# PELT_DRIVE.net
KiCad netlist of a schematic drawn in Altium Designer
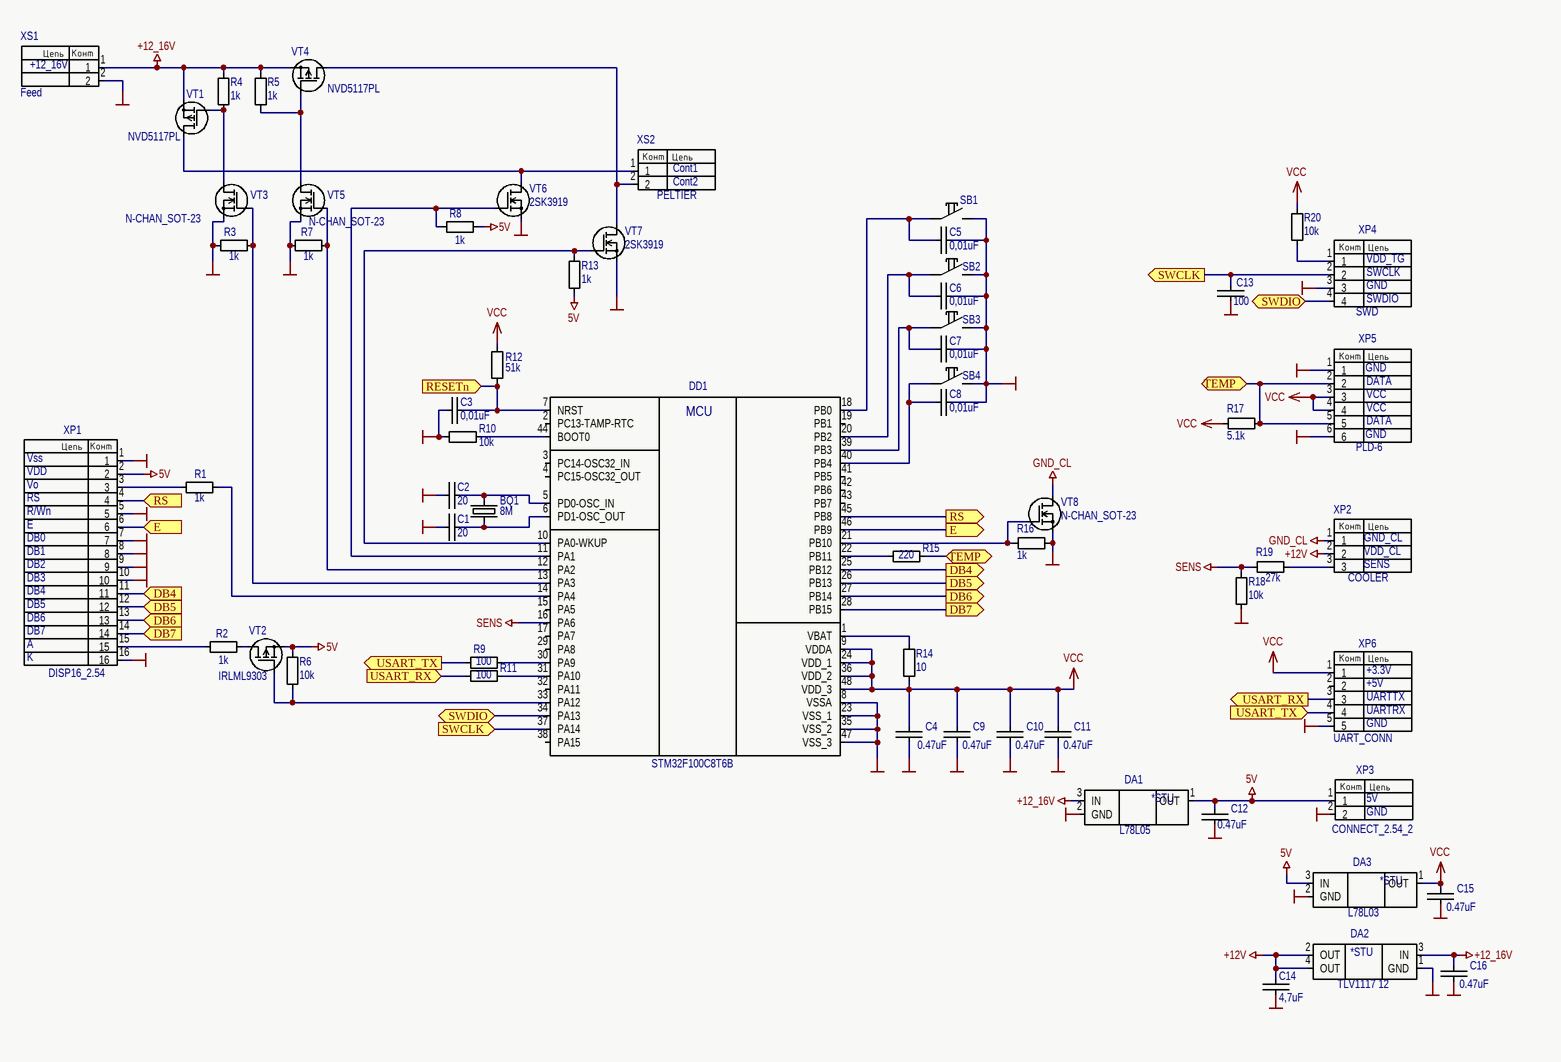
[diagram p0: PELT_DRIVE.SchDoc]

(export (version "E")
  (design (tool "Eeschema 10.0.6"))
  (components
    (comp (ref "BQ1") (value "8M") (footprint "HC 49S") (libsource (lib "PANEL") (part "BQ_HC 49S")))
    (comp (ref "C1")
      (value "20")
      (footprint "Cap_0805")
      (fields (field (name "MANUFACTURER") "AVX") (field (name "PART NUMBER") "08051A200JAT2A"))
      (libsource (lib "PANEL") (part "Cap_0805"))
    )
    (comp (ref "C2")
      (value "20")
      (footprint "Cap_0805")
      (fields (field (name "MANUFACTURER") "AVX") (field (name "PART NUMBER") "08051A200JAT2A"))
      (libsource (lib "PANEL") (part "Cap_0805"))
    )
    (comp (ref "C3")
      (value "0,01uF")
      (footprint "Cap_0805")
      (fields (field (name "MANUFACTURER") "AVX") (field (name "PART NUMBER") "08055C103JAT2A"))
      (libsource (lib "PANEL") (part "Cap_0805"))
    )
    (comp (ref "C4")
      (value "0.47uF")
      (footprint "Cap_0805")
      (fields (field (name "MANUFACTURER") "AVX") (field (name "PART NUMBER") "0805YC475KAT2A"))
      (libsource (lib "PANEL") (part "Cap_0805"))
    )
    (comp (ref "C5")
      (value "0,01uF")
      (footprint "Cap_0805")
      (fields (field (name "MANUFACTURER") "AVX") (field (name "PART NUMBER") "08055C103JAT2A"))
      (libsource (lib "PANEL") (part "Cap_0805"))
    )
    (comp (ref "C6")
      (value "0,01uF")
      (footprint "Cap_0805")
      (fields (field (name "MANUFACTURER") "AVX") (field (name "PART NUMBER") "08055C103JAT2A"))
      (libsource (lib "PANEL") (part "Cap_0805"))
    )
    (comp (ref "C7")
      (value "0,01uF")
      (footprint "Cap_0805")
      (fields (field (name "MANUFACTURER") "AVX") (field (name "PART NUMBER") "08055C103JAT2A"))
      (libsource (lib "PANEL") (part "Cap_0805"))
    )
    (comp (ref "C8")
      (value "0,01uF")
      (footprint "Cap_0805")
      (fields (field (name "MANUFACTURER") "AVX") (field (name "PART NUMBER") "08055C103JAT2A"))
      (libsource (lib "PANEL") (part "Cap_0805"))
    )
    (comp (ref "C9")
      (value "0.47uF")
      (footprint "Cap_0805")
      (fields (field (name "MANUFACTURER") "AVX") (field (name "PART NUMBER") "0805YC475KAT2A"))
      (libsource (lib "PANEL") (part "Cap_0805"))
    )
    (comp (ref "C10")
      (value "0.47uF")
      (footprint "Cap_0805")
      (fields (field (name "MANUFACTURER") "AVX") (field (name "PART NUMBER") "0805YC475KAT2A"))
      (libsource (lib "PANEL") (part "Cap_0805"))
    )
    (comp (ref "C11")
      (value "0.47uF")
      (footprint "Cap_0805")
      (fields (field (name "MANUFACTURER") "AVX") (field (name "PART NUMBER") "0805YC475KAT2A"))
      (libsource (lib "PANEL") (part "Cap_0805"))
    )
    (comp (ref "C12")
      (value "0.47uF")
      (footprint "Cap_0805")
      (fields (field (name "MANUFACTURER") "AVX") (field (name "PART NUMBER") "0805YC475KAT2A"))
      (libsource (lib "PANEL") (part "Cap_0805"))
    )
    (comp (ref "C13")
      (value "100")
      (footprint "Cap_0805")
      (fields (field (name "MANUFACTURER") "AVX") (field (name "PART NUMBER") "08055C101KAT2A"))
      (libsource (lib "PANEL") (part "Cap_0805"))
    )
    (comp (ref "C14")
      (value "4,7uF")
      (footprint "Cap_0805")
      (description "4.7uF 25V X7R 10%")
      (fields (field (name "MANUFACTURER") "AVX") (field (name "PART NUMBER") "0805YC475KAT2A"))
      (libsource (lib "PANEL") (part "Cap_0805"))
    )
    (comp (ref "C15")
      (value "0.47uF")
      (footprint "Cap_0805")
      (fields (field (name "MANUFACTURER") "AVX") (field (name "PART NUMBER") "0805YC475KAT2A"))
      (libsource (lib "PANEL") (part "Cap_0805"))
    )
    (comp (ref "C16")
      (value "0.47uF")
      (footprint "Cap_0805")
      (fields (field (name "MANUFACTURER") "AVX") (field (name "PART NUMBER") "0805YC475KAT2A"))
      (libsource (lib "PANEL") (part "Cap_0805"))
    )
    (comp (ref "DA1") (value "L78L05") (footprint "kren") (libsource (lib "PANEL") (part "kren")))
    (comp (ref "DA2")
      (value "TLV1117 12")
      (footprint "SOT223")
      (description "TLV1117-sot223")
      (fields (field (name "MANUFACTURER") "Microchip") (field (name "PART NUMBER") "TLV1117"))
      (libsource (lib "EIGHT_29") (part "TLV1117"))
    )
    (comp (ref "DA3")
      (value "L78L03")
      (footprint "kren")
      (fields (field (name "PART NUMBER") "L78L05"))
      (libsource (lib "PANEL") (part "kren"))
    )
    (comp (ref "DD1")
      (value "STM32F100C8T6B")
      (footprint "LQFP48")
      (fields (field (name "MANUFACTURER") "Manufacturer") (field (name "PART NUMBER") "Part Number"))
      (libsource (lib "PANEL") (part "STM32F100C8T6B"))
    )
    (comp (ref "R1") (value "1k") (footprint "Res_0805") (libsource (lib "PANEL") (part "Res_0805")))
    (comp (ref "R2") (value "1k") (footprint "Res_0805") (libsource (lib "PANEL") (part "Res_0805")))
    (comp (ref "R3") (value "1k") (footprint "Res_0805") (libsource (lib "PANEL") (part "Res_0805")))
    (comp (ref "R4")
      (value "1k")
      (footprint "Res_0805")
      (fields (field (name "MANUFACTURER") "Vishay") (field (name "PART NUMBER") "SMD 0805"))
      (libsource (lib "") (part "Res_0805_1"))
    )
    (comp (ref "R5") (value "1k") (footprint "Res_0805") (libsource (lib "") (part "Res_0805_1")))
    (comp (ref "R6")
      (value "10k")
      (footprint "Res_0805")
      (fields (field (name "MANUFACTURER") "Vishay") (field (name "PART NUMBER") "CRCW080510K0JNTA"))
      (libsource (lib "PANEL") (part "Res_0805"))
    )
    (comp (ref "R7") (value "1k") (footprint "Res_0805") (libsource (lib "PANEL") (part "Res_0805")))
    (comp (ref "R8")
      (value "1k")
      (footprint "Res_0805")
      (fields (field (name "PART NUMBER") "0805 1k"))
      (libsource (lib "PANEL") (part "Res_0805"))
    )
    (comp (ref "R9") (value "100") (footprint "Res_0805") (libsource (lib "PANEL") (part "Res_0805")))
    (comp (ref "R10")
      (value "10k")
      (footprint "Res_0805")
      (fields (field (name "MANUFACTURER") "Vishay") (field (name "PART NUMBER") "CRCW080510K0JNTA"))
      (libsource (lib "PANEL") (part "Res_0805"))
    )
    (comp (ref "R11") (value "100") (footprint "Res_0805") (libsource (lib "PANEL") (part "Res_0805")))
    (comp (ref "R12")
      (value "51k")
      (footprint "Res_0805")
      (fields (field (name "MANUFACTURER") "Vishay") (field (name "PART NUMBER") "CRCW08055K00JNTA"))
      (libsource (lib "PANEL") (part "Res_0805"))
    )
    (comp (ref "R13")
      (value "1k")
      (footprint "Res_0805")
      (fields (field (name "PART NUMBER") "0805 1k"))
      (libsource (lib "PANEL") (part "Res_0805"))
    )
    (comp (ref "R14")
      (value "10")
      (footprint "Res_0805")
      (fields (field (name "MANUFACTURER") "Vishay") (field (name "PART NUMBER") "CRCW080510R0FKEA"))
      (libsource (lib "PANEL") (part "Res_0805"))
    )
    (comp (ref "R15") (value "220") (footprint "Res_0805") (libsource (lib "PANEL") (part "Res_0805")))
    (comp (ref "R16") (value "1k") (footprint "Res_0805") (libsource (lib "PANEL") (part "Res_0805")))
    (comp (ref "R17")
      (value "5.1k")
      (footprint "Res_0805")
      (fields (field (name "MANUFACTURER") "Vishay") (field (name "PART NUMBER") "CRCW08055K10JNTA"))
      (libsource (lib "PANEL") (part "Res_0805"))
    )
    (comp (ref "R18")
      (value "10k")
      (footprint "Res_0805")
      (fields (field (name "MANUFACTURER") "Vishay") (field (name "PART NUMBER") "CRCW080510K0JNTA"))
      (libsource (lib "PANEL") (part "Res_0805"))
    )
    (comp (ref "R19")
      (value "27k")
      (footprint "Res_0805")
      (fields (field (name "MANUFACTURER") "Vishay") (field (name "PART NUMBER") "CRCW080527K0JNTA"))
      (libsource (lib "PANEL") (part "Res_0805"))
    )
    (comp (ref "R20")
      (value "10k")
      (footprint "Res_0805")
      (fields (field (name "MANUFACTURER") "Vishay") (field (name "PART NUMBER") "CRCW080510K0JNTA"))
      (libsource (lib "PANEL") (part "Res_0805"))
    )
    (comp (ref "SB1")
      (value "BUTTON 4.5x6")
      (footprint "BUTTON 6x4.5")
      (description "Button")
      (libsource (lib "PELT_DRIVE") (part "BUTTON 4.5x6"))
    )
    (comp (ref "SB2")
      (value "BUTTON 4.5x6")
      (footprint "BUTTON 6x4.5")
      (description "Button")
      (libsource (lib "") (part "BUTTON 4.5x6_1"))
    )
    (comp (ref "SB3")
      (value "BUTTON 4.5x6")
      (footprint "BUTTON 6x4.5")
      (description "Button")
      (libsource (lib "") (part "BUTTON 4.5x6_1"))
    )
    (comp (ref "SB4")
      (value "BUTTON 4.5x6")
      (footprint "BUTTON 6x4.5")
      (description "Button")
      (libsource (lib "") (part "BUTTON 4.5x6_1"))
    )
    (comp (ref "VT1")
      (value "NVD5117PL")
      (footprint "TO-252")
      (libsource (lib "PANEL") (part "P-CHAN_TO-252"))
    )
    (comp (ref "VT2")
      (value "IRLML9303")
      (footprint "SOT-23")
      (fields (field (name "PART NUMBER") "IRLML9303TRPBF"))
      (libsource (lib "PSU") (part "P-CHAN_SOT-23"))
    )
    (comp (ref "VT3")
      (value "N-CHAN_SOT-23")
      (footprint "SOT-23")
      (libsource (lib "PANEL") (part "N-CHAN_SOT-23"))
    )
    (comp (ref "VT4") (value "NVD5117PL") (footprint "TO-252") (libsource (lib "") (part "P-CHAN_TO-252_1")))
    (comp (ref "VT5")
      (value "N-CHAN_SOT-23")
      (footprint "SOT-23")
      (libsource (lib "PANEL") (part "N-CHAN_SOT-23"))
    )
    (comp (ref "VT6") (value "2SK3919") (footprint "TO-252") (libsource (lib "PANEL") (part "N-CHAN_TO-252")))
    (comp (ref "VT7") (value "2SK3919") (footprint "TO-252") (libsource (lib "PANEL") (part "N-CHAN_TO-252")))
    (comp (ref "VT8")
      (value "N-CHAN_SOT-23")
      (footprint "SOT-23")
      (libsource (lib "PANEL") (part "N-CHAN_SOT-23"))
    )
    (comp (ref "XP1")
      (value "DISP16_2.54")
      (footprint "DISP16_2.54")
      (libsource (lib "PANEL") (part "DISP16_2.54"))
    )
    (comp (ref "XP2")
      (value "COOLER")
      (footprint "CONN_2.54_3")
      (libsource (lib "PELT_DRIVE") (part "CONNECT_2.54_3"))
    )
    (comp (ref "XP3")
      (value "CONNECT_2.54_2")
      (footprint "CONN_2.54_2")
      (libsource (lib "PANEL") (part "CONNECT_2.54_2"))
    )
    (comp (ref "XP4")
      (value "SWD")
      (footprint "CONN_2.54_4")
      (fields (field (name "MANUFACTURER") "Manufacturer") (field (name "PART NUMBER") "Part Number"))
      (libsource (lib "PANEL") (part "CONNECT_SWD"))
    )
    (comp (ref "XP5")
      (value "PLD-6")
      (footprint "CONN_2.54_6_2")
      (libsource (lib "PANEL") (part "CONNECT_2.54_6_2"))
    )
    (comp (ref "XP6")
      (value "UART_CONN")
      (footprint "CONN_2.54_5")
      (libsource (lib "PANEL") (part "CONNECT_2.54_5"))
    )
    (comp (ref "XS1") (value "Feed") (footprint "PELTIER") (libsource (lib "PANEL") (part "PELTIER")))
    (comp (ref "XS2") (value "PELTIER") (footprint "PELTIER") (libsource (lib "") (part "PELTIER_1")))
  )
  (nets
    (net (code "1") (name "+12V") (class "Default")
      (node (ref "C14") (pin "2") (pinfunction "2_2") (pintype "passive"))
      (node (ref "DA2") (pin "2") (pinfunction "OUT_2") (pintype "passive"))
      (node (ref "DA2") (pin "4") (pinfunction "OUT_4") (pintype "passive"))
      (node (ref "XP2") (pin "2") (pinfunction "2_2") (pintype "passive"))
    )
    (net (code "2") (name "+12_16V") (class "Default")
      (node (ref "C16") (pin "2") (pinfunction "2_2") (pintype "passive"))
      (node (ref "DA1") (pin "3") (pinfunction "IN_3") (pintype "passive"))
      (node (ref "DA2") (pin "3") (pinfunction "IN_3") (pintype "passive"))
      (node (ref "R4") (pin "1") (pinfunction "1_1") (pintype "passive"))
      (node (ref "R5") (pin "2") (pinfunction "2_2") (pintype "passive"))
      (node (ref "VT1") (pin "3") (pinfunction "3_3") (pintype "passive"))
      (node (ref "VT4") (pin "3") (pinfunction "3_3") (pintype "passive"))
      (node (ref "XS1") (pin "1") (pinfunction "1_1") (pintype "passive"))
    )
    (net (code "3") (name "/DB4") (class "Default")
      (node (ref "DD1") (pin "25") (pinfunction "PB12_25") (pintype "passive"))
      (node (ref "XP1") (pin "11") (pinfunction "11_11") (pintype "passive"))
    )
    (net (code "4") (name "/DB5") (class "Default")
      (node (ref "DD1") (pin "26") (pinfunction "PB13_26") (pintype "passive"))
      (node (ref "XP1") (pin "12") (pinfunction "12_12") (pintype "passive"))
    )
    (net (code "5") (name "/DB6") (class "Default")
      (node (ref "DD1") (pin "27") (pinfunction "PB14_27") (pintype "passive"))
      (node (ref "XP1") (pin "13") (pinfunction "13_13") (pintype "passive"))
    )
    (net (code "6") (name "/DB7") (class "Default")
      (node (ref "DD1") (pin "28") (pinfunction "PB15_28") (pintype "passive"))
      (node (ref "XP1") (pin "14") (pinfunction "14_14") (pintype "passive"))
    )
    (net (code "7") (name "/E") (class "Default")
      (node (ref "DD1") (pin "46") (pinfunction "PB9_46") (pintype "passive"))
      (node (ref "XP1") (pin "6") (pinfunction "6_6") (pintype "passive"))
    )
    (net (code "8") (name "/RESETn") (class "Default")
      (node (ref "C3") (pin "2") (pinfunction "2_2") (pintype "passive"))
      (node (ref "DD1") (pin "7") (pinfunction "NRST_7") (pintype "passive"))
      (node (ref "R12") (pin "1") (pinfunction "1_1") (pintype "passive"))
    )
    (net (code "9") (name "/RS") (class "Default")
      (node (ref "DD1") (pin "45") (pinfunction "PB8_45") (pintype "passive"))
      (node (ref "XP1") (pin "4") (pinfunction "4_4") (pintype "passive"))
    )
    (net (code "10") (name "/SWCLK") (class "Default")
      (node (ref "C13") (pin "2") (pinfunction "2_2") (pintype "passive"))
      (node (ref "DD1") (pin "37") (pinfunction "PA14_37") (pintype "passive"))
      (node (ref "XP4") (pin "2") (pinfunction "2_2") (pintype "passive"))
    )
    (net (code "11") (name "/SWDIO") (class "Default")
      (node (ref "DD1") (pin "34") (pinfunction "PA13_34") (pintype "passive"))
      (node (ref "XP4") (pin "4") (pinfunction "4_4") (pintype "passive"))
    )
    (net (code "12") (name "/TEMP") (class "Default")
      (node (ref "R15") (pin "1") (pinfunction "1_1") (pintype "passive"))
      (node (ref "R17") (pin "1") (pinfunction "1_1") (pintype "passive"))
      (node (ref "XP5") (pin "2") (pinfunction "2_2") (pintype "passive"))
      (node (ref "XP5") (pin "5") (pinfunction "5_5") (pintype "passive"))
    )
    (net (code "13") (name "/USART_RX") (class "Default")
      (node (ref "R11") (pin "1") (pinfunction "1_1") (pintype "passive"))
      (node (ref "XP6") (pin "3") (pinfunction "3_3") (pintype "passive"))
    )
    (net (code "14") (name "/USART_TX") (class "Default")
      (node (ref "R9") (pin "1") (pinfunction "1_1") (pintype "passive"))
      (node (ref "XP6") (pin "4") (pinfunction "4_4") (pintype "passive"))
    )
    (net (code "15") (name "5V") (class "Default")
      (node (ref "C12") (pin "2") (pinfunction "2_2") (pintype "passive"))
      (node (ref "DA1") (pin "1") (pinfunction "OUT_1") (pintype "passive"))
      (node (ref "DA3") (pin "3") (pinfunction "IN_3") (pintype "passive"))
      (node (ref "R13") (pin "1") (pinfunction "1_1") (pintype "passive"))
      (node (ref "R6") (pin "1") (pinfunction "1_1") (pintype "passive"))
      (node (ref "R8") (pin "2") (pinfunction "2_2") (pintype "passive"))
      (node (ref "VT2") (pin "2") (pinfunction "2_2") (pintype "passive"))
      (node (ref "XP1") (pin "2") (pinfunction "2_2") (pintype "passive"))
      (node (ref "XP3") (pin "1") (pinfunction "1_1") (pintype "passive"))
    )
    (net (code "16") (name "GND") (class "Default")
      (node (ref "C1") (pin "1") (pinfunction "1_1") (pintype "passive"))
      (node (ref "C10") (pin "1") (pinfunction "1_1") (pintype "passive"))
      (node (ref "C11") (pin "1") (pinfunction "1_1") (pintype "passive"))
      (node (ref "C12") (pin "1") (pinfunction "1_1") (pintype "passive"))
      (node (ref "C13") (pin "1") (pinfunction "1_1") (pintype "passive"))
      (node (ref "C14") (pin "1") (pinfunction "1_1") (pintype "passive"))
      (node (ref "C15") (pin "1") (pinfunction "1_1") (pintype "passive"))
      (node (ref "C16") (pin "1") (pinfunction "1_1") (pintype "passive"))
      (node (ref "C2") (pin "1") (pinfunction "1_1") (pintype "passive"))
      (node (ref "C3") (pin "1") (pinfunction "1_1") (pintype "passive"))
      (node (ref "C4") (pin "1") (pinfunction "1_1") (pintype "passive"))
      (node (ref "C5") (pin "2") (pinfunction "2_2") (pintype "passive"))
      (node (ref "C6") (pin "2") (pinfunction "2_2") (pintype "passive"))
      (node (ref "C7") (pin "2") (pinfunction "2_2") (pintype "passive"))
      (node (ref "C8") (pin "2") (pinfunction "2_2") (pintype "passive"))
      (node (ref "C9") (pin "1") (pinfunction "1_1") (pintype "passive"))
      (node (ref "DA1") (pin "2") (pinfunction "GND_2") (pintype "passive"))
      (node (ref "DA2") (pin "1") (pinfunction "GND_1") (pintype "passive"))
      (node (ref "DA3") (pin "2") (pinfunction "GND_2") (pintype "passive"))
      (node (ref "DD1") (pin "23") (pinfunction "VSS_1_23") (pintype "passive"))
      (node (ref "DD1") (pin "35") (pinfunction "VSS_2_35") (pintype "passive"))
      (node (ref "DD1") (pin "47") (pinfunction "VSS_3_47") (pintype "passive"))
      (node (ref "DD1") (pin "8") (pinfunction "VSSA_8") (pintype "passive"))
      (node (ref "R10") (pin "2") (pinfunction "2_2") (pintype "passive"))
      (node (ref "R16") (pin "2") (pinfunction "2_2") (pintype "passive"))
      (node (ref "R18") (pin "1") (pinfunction "1_1") (pintype "passive"))
      (node (ref "R3") (pin "2") (pinfunction "2_2") (pintype "passive"))
      (node (ref "R7") (pin "1") (pinfunction "1_1") (pintype "passive"))
      (node (ref "SB1") (pin "2") (pinfunction "IN_2") (pintype "passive"))
      (node (ref "SB2") (pin "2") (pinfunction "IN_2") (pintype "passive"))
      (node (ref "SB3") (pin "2") (pinfunction "IN_2") (pintype "passive"))
      (node (ref "SB4") (pin "2") (pinfunction "IN_2") (pintype "passive"))
      (node (ref "VT3") (pin "2") (pinfunction "2_2") (pintype "passive"))
      (node (ref "VT5") (pin "2") (pinfunction "2_2") (pintype "passive"))
      (node (ref "VT6") (pin "3") (pinfunction "3_3") (pintype "passive"))
      (node (ref "VT7") (pin "3") (pinfunction "3_3") (pintype "passive"))
      (node (ref "VT8") (pin "2") (pinfunction "2_2") (pintype "passive"))
      (node (ref "XP1") (pin "1") (pinfunction "1_1") (pintype "passive"))
      (node (ref "XP1") (pin "10") (pinfunction "10_10") (pintype "passive"))
      (node (ref "XP1") (pin "16") (pinfunction "16_16") (pintype "passive"))
      (node (ref "XP1") (pin "5") (pinfunction "5_5") (pintype "passive"))
      (node (ref "XP1") (pin "7") (pinfunction "7_7") (pintype "passive"))
      (node (ref "XP1") (pin "8") (pinfunction "8_8") (pintype "passive"))
      (node (ref "XP1") (pin "9") (pinfunction "9_9") (pintype "passive"))
      (node (ref "XP3") (pin "2") (pinfunction "2_2") (pintype "passive"))
      (node (ref "XP4") (pin "3") (pinfunction "3_3") (pintype "passive"))
      (node (ref "XP5") (pin "1") (pinfunction "1_1") (pintype "passive"))
      (node (ref "XP5") (pin "6") (pinfunction "6_6") (pintype "passive"))
      (node (ref "XP6") (pin "5") (pinfunction "5_5") (pintype "passive"))
      (node (ref "XS1") (pin "2") (pinfunction "2_2") (pintype "passive"))
    )
    (net (code "17") (name "GND_CL") (class "Default")
      (node (ref "VT8") (pin "3") (pinfunction "3_3") (pintype "passive"))
      (node (ref "XP2") (pin "1") (pinfunction "1_1") (pintype "passive"))
    )
    (net (code "18") (name "Net-(DD1-BOOT0)") (class "Default")
      (node (ref "DD1") (pin "44") (pinfunction "BOOT0_44") (pintype "passive"))
      (node (ref "R10") (pin "1") (pinfunction "1_1") (pintype "passive"))
    )
    (net (code "19") (name "Net-(DD1-PA0-WKUP)") (class "Default")
      (node (ref "DD1") (pin "10") (pinfunction "PA0-WKUP_10") (pintype "passive"))
      (node (ref "R13") (pin "2") (pinfunction "2_2") (pintype "passive"))
      (node (ref "VT7") (pin "1") (pinfunction "1_1") (pintype "passive"))
    )
    (net (code "20") (name "Net-(DD1-PA1)") (class "Default")
      (node (ref "DD1") (pin "11") (pinfunction "PA1_11") (pintype "passive"))
      (node (ref "R8") (pin "1") (pinfunction "1_1") (pintype "passive"))
      (node (ref "VT6") (pin "1") (pinfunction "1_1") (pintype "passive"))
    )
    (net (code "21") (name "Net-(DD1-PA2)") (class "Default")
      (node (ref "DD1") (pin "12") (pinfunction "PA2_12") (pintype "passive"))
      (node (ref "R7") (pin "2") (pinfunction "2_2") (pintype "passive"))
      (node (ref "VT5") (pin "1") (pinfunction "1_1") (pintype "passive"))
    )
    (net (code "22") (name "Net-(DD1-PA3)") (class "Default")
      (node (ref "DD1") (pin "13") (pinfunction "PA3_13") (pintype "passive"))
      (node (ref "R3") (pin "1") (pinfunction "1_1") (pintype "passive"))
      (node (ref "VT3") (pin "1") (pinfunction "1_1") (pintype "passive"))
    )
    (net (code "23") (name "Net-(DD1-PA4)") (class "Default")
      (node (ref "DD1") (pin "14") (pinfunction "PA4_14") (pintype "passive"))
      (node (ref "R1") (pin "1") (pinfunction "1_1") (pintype "passive"))
    )
    (net (code "24") (name "Net-(DD1-PA9)") (class "Default")
      (node (ref "DD1") (pin "30") (pinfunction "PA9_30") (pintype "passive"))
      (node (ref "R9") (pin "2") (pinfunction "2_2") (pintype "passive"))
    )
    (net (code "25") (name "Net-(DD1-PA10)") (class "Default")
      (node (ref "DD1") (pin "31") (pinfunction "PA10_31") (pintype "passive"))
      (node (ref "R11") (pin "2") (pinfunction "2_2") (pintype "passive"))
    )
    (net (code "26") (name "Net-(DD1-PA12)") (class "Default")
      (node (ref "DD1") (pin "33") (pinfunction "PA12_33") (pintype "passive"))
      (node (ref "R6") (pin "2") (pinfunction "2_2") (pintype "passive"))
      (node (ref "VT2") (pin "1") (pinfunction "1_1") (pintype "passive"))
    )
    (net (code "27") (name "Net-(DD1-PB0)") (class "Default")
      (node (ref "C5") (pin "1") (pinfunction "1_1") (pintype "passive"))
      (node (ref "DD1") (pin "18") (pinfunction "PB0_18") (pintype "passive"))
      (node (ref "SB1") (pin "1") (pinfunction "OUT_1") (pintype "passive"))
    )
    (net (code "28") (name "Net-(DD1-PB2)") (class "Default")
      (node (ref "C6") (pin "1") (pinfunction "1_1") (pintype "passive"))
      (node (ref "DD1") (pin "20") (pinfunction "PB2_20") (pintype "passive"))
      (node (ref "SB2") (pin "1") (pinfunction "OUT_1") (pintype "passive"))
    )
    (net (code "29") (name "Net-(DD1-PB3)") (class "Default")
      (node (ref "C7") (pin "1") (pinfunction "1_1") (pintype "passive"))
      (node (ref "DD1") (pin "39") (pinfunction "PB3_39") (pintype "passive"))
      (node (ref "SB3") (pin "1") (pinfunction "OUT_1") (pintype "passive"))
    )
    (net (code "30") (name "Net-(DD1-PB4)") (class "Default")
      (node (ref "C8") (pin "1") (pinfunction "1_1") (pintype "passive"))
      (node (ref "DD1") (pin "40") (pinfunction "PB4_40") (pintype "passive"))
      (node (ref "SB4") (pin "1") (pinfunction "OUT_1") (pintype "passive"))
    )
    (net (code "31") (name "Net-(DD1-PB10)") (class "Default")
      (node (ref "DD1") (pin "21") (pinfunction "PB10_21") (pintype "passive"))
      (node (ref "R16") (pin "1") (pinfunction "1_1") (pintype "passive"))
      (node (ref "VT8") (pin "1") (pinfunction "1_1") (pintype "passive"))
    )
    (net (code "32") (name "Net-(DD1-PB11)") (class "Default")
      (node (ref "DD1") (pin "22") (pinfunction "PB11_22") (pintype "passive"))
      (node (ref "R15") (pin "2") (pinfunction "2_2") (pintype "passive"))
    )
    (net (code "33") (name "Net-(DD1-PD0-OSC_IN)") (class "Default")
      (node (ref "BQ1") (pin "2") (pinfunction "2_2") (pintype "passive"))
      (node (ref "C2") (pin "2") (pinfunction "2_2") (pintype "passive"))
      (node (ref "DD1") (pin "5") (pinfunction "PD0-OSC_IN_5") (pintype "passive"))
    )
    (net (code "34") (name "Net-(DD1-PD1-OSC_OUT)") (class "Default")
      (node (ref "BQ1") (pin "1") (pinfunction "1_1") (pintype "passive"))
      (node (ref "C1") (pin "2") (pinfunction "2_2") (pintype "passive"))
      (node (ref "DD1") (pin "6") (pinfunction "PD1-OSC_OUT_6") (pintype "passive"))
    )
    (net (code "35") (name "Net-(DD1-VBAT)") (class "Default")
      (node (ref "DD1") (pin "1") (pinfunction "VBAT_1") (pintype "passive"))
      (node (ref "R14") (pin "1") (pinfunction "1_1") (pintype "passive"))
    )
    (net (code "36") (name "Net-(R1-Pad2)") (class "Default")
      (node (ref "R1") (pin "2") (pinfunction "2_2") (pintype "passive"))
      (node (ref "XP1") (pin "3") (pinfunction "3_3") (pintype "passive"))
    )
    (net (code "37") (name "Net-(R2-Pad1)") (class "Default")
      (node (ref "R2") (pin "1") (pinfunction "1_1") (pintype "passive"))
      (node (ref "VT2") (pin "3") (pinfunction "3_3") (pintype "passive"))
    )
    (net (code "38") (name "Net-(R2-Pad2)") (class "Default")
      (node (ref "R2") (pin "2") (pinfunction "2_2") (pintype "passive"))
      (node (ref "XP1") (pin "15") (pinfunction "15_15") (pintype "passive"))
    )
    (net (code "39") (name "Net-(R4-Pad2)") (class "Default")
      (node (ref "R4") (pin "2") (pinfunction "2_2") (pintype "passive"))
      (node (ref "VT1") (pin "1") (pinfunction "1_1") (pintype "passive"))
      (node (ref "VT3") (pin "3") (pinfunction "3_3") (pintype "passive"))
    )
    (net (code "40") (name "Net-(R5-Pad1)") (class "Default")
      (node (ref "R5") (pin "1") (pinfunction "1_1") (pintype "passive"))
      (node (ref "VT4") (pin "1") (pinfunction "1_1") (pintype "passive"))
      (node (ref "VT5") (pin "3") (pinfunction "3_3") (pintype "passive"))
    )
    (net (code "41") (name "Net-(R19-Pad1)") (class "Default")
      (node (ref "R19") (pin "1") (pinfunction "1_1") (pintype "passive"))
      (node (ref "XP2") (pin "3") (pinfunction "3_3") (pintype "passive"))
    )
    (net (code "42") (name "Net-(R20-Pad1)") (class "Default")
      (node (ref "R20") (pin "1") (pinfunction "1_1") (pintype "passive"))
      (node (ref "XP4") (pin "1") (pinfunction "1_1") (pintype "passive"))
    )
    (net (code "43") (name "Net-(VT1-Pad2)") (class "Default")
      (node (ref "VT1") (pin "2") (pinfunction "2_2") (pintype "passive"))
      (node (ref "VT6") (pin "2") (pinfunction "2_2") (pintype "passive"))
      (node (ref "XS2") (pin "1") (pinfunction "1_1") (pintype "passive"))
    )
    (net (code "44") (name "Net-(VT4-Pad2)") (class "Default")
      (node (ref "VT4") (pin "2") (pinfunction "2_2") (pintype "passive"))
      (node (ref "VT7") (pin "2") (pinfunction "2_2") (pintype "passive"))
      (node (ref "XS2") (pin "2") (pinfunction "2_2") (pintype "passive"))
    )
    (net (code "45") (name "SENS") (class "Default")
      (node (ref "DD1") (pin "16") (pinfunction "PA6_16") (pintype "passive"))
      (node (ref "R18") (pin "2") (pinfunction "2_2") (pintype "passive"))
      (node (ref "R19") (pin "2") (pinfunction "2_2") (pintype "passive"))
    )
    (net (code "46") (name "VCC") (class "Default")
      (node (ref "C10") (pin "2") (pinfunction "2_2") (pintype "passive"))
      (node (ref "C11") (pin "2") (pinfunction "2_2") (pintype "passive"))
      (node (ref "C15") (pin "2") (pinfunction "2_2") (pintype "passive"))
      (node (ref "C4") (pin "2") (pinfunction "2_2") (pintype "passive"))
      (node (ref "C9") (pin "2") (pinfunction "2_2") (pintype "passive"))
      (node (ref "DA3") (pin "1") (pinfunction "OUT_1") (pintype "passive"))
      (node (ref "DD1") (pin "24") (pinfunction "VDD_1_24") (pintype "passive"))
      (node (ref "DD1") (pin "36") (pinfunction "VDD_2_36") (pintype "passive"))
      (node (ref "DD1") (pin "48") (pinfunction "VDD_3_48") (pintype "passive"))
      (node (ref "DD1") (pin "9") (pinfunction "VDDA_9") (pintype "passive"))
      (node (ref "R12") (pin "2") (pinfunction "2_2") (pintype "passive"))
      (node (ref "R14") (pin "2") (pinfunction "2_2") (pintype "passive"))
      (node (ref "R17") (pin "2") (pinfunction "2_2") (pintype "passive"))
      (node (ref "R20") (pin "2") (pinfunction "2_2") (pintype "passive"))
      (node (ref "XP5") (pin "3") (pinfunction "3_3") (pintype "passive"))
      (node (ref "XP5") (pin "4") (pinfunction "4_4") (pintype "passive"))
      (node (ref "XP6") (pin "1") (pinfunction "1_1") (pintype "passive"))
    )
    (net (code "47") (name "unconnected-(DD1-PA5-Pad15)") (class "Default")
      (node (ref "DD1") (pin "15") (pinfunction "PA5_15") (pintype "passive"))
    )
    (net (code "48") (name "unconnected-(DD1-PA7-Pad17)") (class "Default")
      (node (ref "DD1") (pin "17") (pinfunction "PA7_17") (pintype "passive"))
    )
    (net (code "49") (name "unconnected-(DD1-PA8-Pad29)") (class "Default")
      (node (ref "DD1") (pin "29") (pinfunction "PA8_29") (pintype "passive"))
    )
    (net (code "50") (name "unconnected-(DD1-PA11-Pad32)") (class "Default")
      (node (ref "DD1") (pin "32") (pinfunction "PA11_32") (pintype "passive"))
    )
    (net (code "51") (name "unconnected-(DD1-PA15-Pad38)") (class "Default")
      (node (ref "DD1") (pin "38") (pinfunction "PA15_38") (pintype "passive"))
    )
    (net (code "52") (name "unconnected-(DD1-PB1-Pad19)") (class "Default")
      (node (ref "DD1") (pin "19") (pinfunction "PB1_19") (pintype "passive"))
    )
    (net (code "53") (name "unconnected-(DD1-PB5-Pad41)") (class "Default")
      (node (ref "DD1") (pin "41") (pinfunction "PB5_41") (pintype "passive"))
    )
    (net (code "54") (name "unconnected-(DD1-PB6-Pad42)") (class "Default")
      (node (ref "DD1") (pin "42") (pinfunction "PB6_42") (pintype "passive"))
    )
    (net (code "55") (name "unconnected-(DD1-PB7-Pad43)") (class "Default")
      (node (ref "DD1") (pin "43") (pinfunction "PB7_43") (pintype "passive"))
    )
    (net (code "56") (name "unconnected-(DD1-PC13-TAMP-RTC-Pad2)") (class "Default")
      (node (ref "DD1") (pin "2") (pinfunction "PC13-TAMP-RTC_2") (pintype "passive"))
    )
    (net (code "57") (name "unconnected-(DD1-PC14-OSC32_IN-Pad3)") (class "Default")
      (node (ref "DD1") (pin "3") (pinfunction "PC14-OSC32_IN_3") (pintype "passive"))
    )
    (net (code "58") (name "unconnected-(DD1-PC15-OSC32_OUT-Pad4)") (class "Default")
      (node (ref "DD1") (pin "4") (pinfunction "PC15-OSC32_OUT_4") (pintype "passive"))
    )
    (net (code "59") (name "unconnected-(XP6-Pad2)") (class "Default")
      (node (ref "XP6") (pin "2") (pinfunction "2_2") (pintype "passive"))
    )
  )
)
